# test.net
KiCad netlist of a schematic drawn in EAGLE
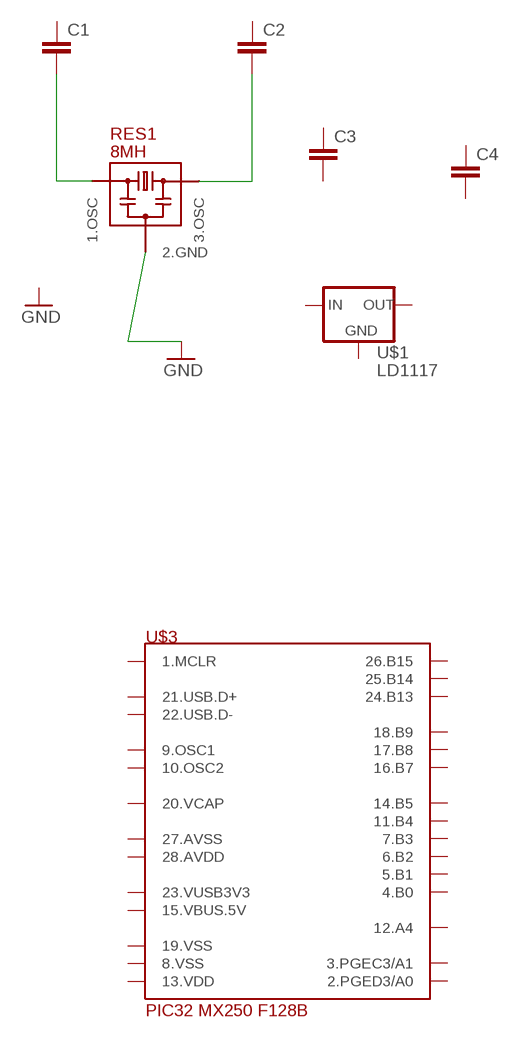
[diagram p0: schematic, sheet 1]

(export (version "E")
  (design (tool "Eeschema 10.0.6"))
  (components
    (comp (ref "C1")
      (value "CAPPTH1")
      (footprint "eagle-import:CAP-PTH-5MM")
      (libsource (lib "eagle-import") (part "CAPPTH1"))
    )
    (comp (ref "C2")
      (value "CAPPTH1")
      (footprint "eagle-import:CAP-PTH-5MM")
      (libsource (lib "eagle-import") (part "CAPPTH1"))
    )
    (comp (ref "C3")
      (value "CAPPTH1")
      (footprint "eagle-import:CAP-PTH-5MM")
      (libsource (lib "eagle-import") (part "CAPPTH1"))
    )
    (comp (ref "C4")
      (value "CAPPTH")
      (footprint "eagle-import:CAP-PTH-SMALL")
      (libsource (lib "eagle-import") (part "CAPPTH"))
    )
    (comp (ref "RES1")
      (value "8MH")
      (footprint "eagle-import:RESONATOR_PTH")
      (libsource (lib "eagle-import") (part "RESONATOR"))
    )
    (comp (ref "U$1")
      (value "LD1117")
      (footprint "eagle-import:TO220")
      (libsource (lib "eagle-import") (part "LD1117"))
    )
    (comp (ref "U$3")
      (value "PIC32MX250F128B")
      (footprint "eagle-import:DIL_28_3_JOHN")
      (libsource (lib "eagle-import") (part "PIC32MX250F128B"))
    )
  )
  (nets
    (net (code "1") (name "/8.VSS") (class "Default")
      (node (ref "U$3") (pin "P$8") (pinfunction "8.VSS_P$8") (pintype "power_in"))
    )
    (net (code "2") (name "/13.VDD") (class "Default")
      (node (ref "U$3") (pin "P$13") (pinfunction "13.VDD_P$13") (pintype "power_in"))
    )
    (net (code "3") (name "/15.VBUS.5V") (class "Default")
      (node (ref "U$3") (pin "P$15") (pinfunction "15.VBUS.5V_P$15") (pintype "power_in"))
    )
    (net (code "4") (name "/19.VSS") (class "Default")
      (node (ref "U$3") (pin "P$19") (pinfunction "19.VSS_P$19") (pintype "power_in"))
    )
    (net (code "5") (name "/20.VCAP") (class "Default")
      (node (ref "U$3") (pin "P$20") (pinfunction "20.VCAP_P$20") (pintype "power_in"))
    )
    (net (code "6") (name "/23.VUSB3V3") (class "Default")
      (node (ref "U$3") (pin "P$23") (pinfunction "23.VUSB3V3_P$23") (pintype "power_in"))
    )
    (net (code "7") (name "/27.AVSS") (class "Default")
      (node (ref "U$3") (pin "P$27") (pinfunction "27.AVSS_P$27") (pintype "power_in"))
    )
    (net (code "8") (name "/28.AVDD") (class "Default")
      (node (ref "U$3") (pin "P$28") (pinfunction "28.AVDD_P$28") (pintype "power_in"))
    )
    (net (code "9") (name "GND") (class "Default")
      (node (ref "RES1") (pin "P$2") (pinfunction "2.GND_P$2") (pintype "power_in"))
    )
    (net (code "10") (name "Net-(RES1-1.OSC)") (class "Default")
      (node (ref "C1") (pin "2") (pinfunction "2_2") (pintype "passive"))
      (node (ref "RES1") (pin "P$3") (pinfunction "1.OSC_P$3") (pintype "bidirectional"))
    )
    (net (code "11") (name "Net-(RES1-3.OSC)") (class "Default")
      (node (ref "C2") (pin "2") (pinfunction "2_2") (pintype "passive"))
      (node (ref "RES1") (pin "P$1") (pinfunction "3.OSC_P$1") (pintype "bidirectional"))
    )
    (net (code "12") (name "unconnected-(C1-Pad1)") (class "Default")
      (node (ref "C1") (pin "1") (pinfunction "1_1") (pintype "passive"))
    )
    (net (code "13") (name "unconnected-(C2-Pad1)") (class "Default")
      (node (ref "C2") (pin "1") (pinfunction "1_1") (pintype "passive"))
    )
    (net (code "14") (name "unconnected-(C3-Pad1)") (class "Default")
      (node (ref "C3") (pin "1") (pinfunction "1_1") (pintype "passive"))
    )
    (net (code "15") (name "unconnected-(C3-Pad2)") (class "Default")
      (node (ref "C3") (pin "2") (pinfunction "2_2") (pintype "passive"))
    )
    (net (code "16") (name "unconnected-(C4-Pad1)") (class "Default")
      (node (ref "C4") (pin "1") (pinfunction "1_1") (pintype "passive"))
    )
    (net (code "17") (name "unconnected-(C4-Pad2)") (class "Default")
      (node (ref "C4") (pin "2") (pinfunction "2_2") (pintype "passive"))
    )
    (net (code "18") (name "unconnected-(U$1-GND-Pad1)") (class "Default")
      (node (ref "U$1") (pin "1") (pinfunction "GND_1") (pintype "input"))
    )
    (net (code "19") (name "unconnected-(U$1-IN-Pad3)") (class "Default")
      (node (ref "U$1") (pin "3") (pinfunction "IN_3") (pintype "input"))
    )
    (net (code "20") (name "unconnected-(U$1-OUT-Pad2)") (class "Default")
      (node (ref "U$1") (pin "2") (pinfunction "OUT_2") (pintype "output"))
    )
    (net (code "21") (name "unconnected-(U$3-1.MCLR-PadP$1)") (class "Default")
      (node (ref "U$3") (pin "P$1") (pinfunction "1.MCLR_P$1") (pintype "input"))
    )
    (net (code "22") (name "unconnected-(U$3-2.PGED3{slash}A0-PadP$2)") (class "Default")
      (node (ref "U$3") (pin "P$2") (pinfunction "2.PGED3/A0_P$2") (pintype "bidirectional"))
    )
    (net (code "23") (name "unconnected-(U$3-3.PGEC3{slash}A1-PadP$3)") (class "Default")
      (node (ref "U$3") (pin "P$3") (pinfunction "3.PGEC3/A1_P$3") (pintype "bidirectional"))
    )
    (net (code "24") (name "unconnected-(U$3-4.B0-PadP$4)") (class "Default")
      (node (ref "U$3") (pin "P$4") (pinfunction "4.B0_P$4") (pintype "bidirectional"))
    )
    (net (code "25") (name "unconnected-(U$3-5.B1-PadP$5)") (class "Default")
      (node (ref "U$3") (pin "P$5") (pinfunction "5.B1_P$5") (pintype "bidirectional"))
    )
    (net (code "26") (name "unconnected-(U$3-6.B2-PadP$6)") (class "Default")
      (node (ref "U$3") (pin "P$6") (pinfunction "6.B2_P$6") (pintype "bidirectional"))
    )
    (net (code "27") (name "unconnected-(U$3-7.B3-PadP$7)") (class "Default")
      (node (ref "U$3") (pin "P$7") (pinfunction "7.B3_P$7") (pintype "bidirectional"))
    )
    (net (code "28") (name "unconnected-(U$3-9.OSC1-PadP$9)") (class "Default")
      (node (ref "U$3") (pin "P$9") (pinfunction "9.OSC1_P$9") (pintype "input"))
    )
    (net (code "29") (name "unconnected-(U$3-10.OSC2-PadP$10)") (class "Default")
      (node (ref "U$3") (pin "P$10") (pinfunction "10.OSC2_P$10") (pintype "input"))
    )
    (net (code "30") (name "unconnected-(U$3-11.B4-PadP$11)") (class "Default")
      (node (ref "U$3") (pin "P$11") (pinfunction "11.B4_P$11") (pintype "bidirectional"))
    )
    (net (code "31") (name "unconnected-(U$3-12.A4-PadP$12)") (class "Default")
      (node (ref "U$3") (pin "P$12") (pinfunction "12.A4_P$12") (pintype "bidirectional"))
    )
    (net (code "32") (name "unconnected-(U$3-14.B5-PadP$14)") (class "Default")
      (node (ref "U$3") (pin "P$14") (pinfunction "14.B5_P$14") (pintype "bidirectional"))
    )
    (net (code "33") (name "unconnected-(U$3-16.B7-PadP$16)") (class "Default")
      (node (ref "U$3") (pin "P$16") (pinfunction "16.B7_P$16") (pintype "bidirectional"))
    )
    (net (code "34") (name "unconnected-(U$3-17.B8-PadP$17)") (class "Default")
      (node (ref "U$3") (pin "P$17") (pinfunction "17.B8_P$17") (pintype "bidirectional"))
    )
    (net (code "35") (name "unconnected-(U$3-18.B9-PadP$18)") (class "Default")
      (node (ref "U$3") (pin "P$18") (pinfunction "18.B9_P$18") (pintype "bidirectional"))
    )
    (net (code "36") (name "unconnected-(U$3-21.USB.D+-PadP$21)") (class "Default")
      (node (ref "U$3") (pin "P$21") (pinfunction "21.USB.D+_P$21") (pintype "bidirectional"))
    )
    (net (code "37") (name "unconnected-(U$3-22.USB.D--PadP$22)") (class "Default")
      (node (ref "U$3") (pin "P$22") (pinfunction "22.USB.D-_P$22") (pintype "bidirectional"))
    )
    (net (code "38") (name "unconnected-(U$3-24.B13-PadP$24)") (class "Default")
      (node (ref "U$3") (pin "P$24") (pinfunction "24.B13_P$24") (pintype "bidirectional"))
    )
    (net (code "39") (name "unconnected-(U$3-25.B14-PadP$25)") (class "Default")
      (node (ref "U$3") (pin "P$25") (pinfunction "25.B14_P$25") (pintype "bidirectional"))
    )
    (net (code "40") (name "unconnected-(U$3-26.B15-PadP$26)") (class "Default")
      (node (ref "U$3") (pin "P$26") (pinfunction "26.B15_P$26") (pintype "bidirectional"))
    )
  )
)
